# ADC_FILTER.net
KiCad netlist of a schematic drawn in Altium Designer
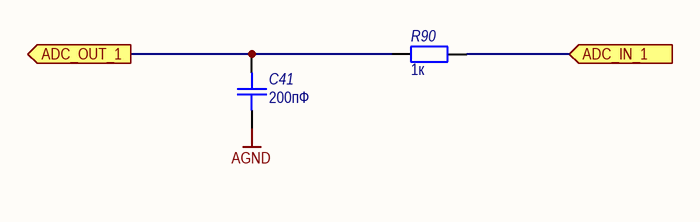
[diagram p0: ADC_FILTER.SchDoc]

(export (version "E")
  (design (tool "Eeschema 10.0.6"))
  (components
    (comp (ref "C41")
      (value "200пФ")
      (footprint "SMD_0805")
      (description "Capacitor")
      (libsource (lib "Passive") (part "Capacitor"))
    )
    (comp (ref "R90")
      (value "1к")
      (footprint "SMD_0805")
      (description "Resistor")
      (libsource (lib "Passive") (part "Resistor"))
    )
  )
  (nets
    (net (code "1") (name "/ADC_IN_1") (class "Default")
      (node (ref "R90") (pin "2") (pinfunction "2_2") (pintype "passive"))
    )
    (net (code "2") (name "/ADC_OUT_1") (class "Default")
      (node (ref "C41") (pin "2") (pinfunction "2_2") (pintype "passive"))
      (node (ref "R90") (pin "1") (pinfunction "1_1") (pintype "passive"))
    )
    (net (code "3") (name "AGND") (class "Default")
      (node (ref "C41") (pin "1") (pinfunction "1_1") (pintype "passive"))
    )
  )
)
